# 07-FPGA.net
KiCad netlist of a schematic drawn in Altium Designer
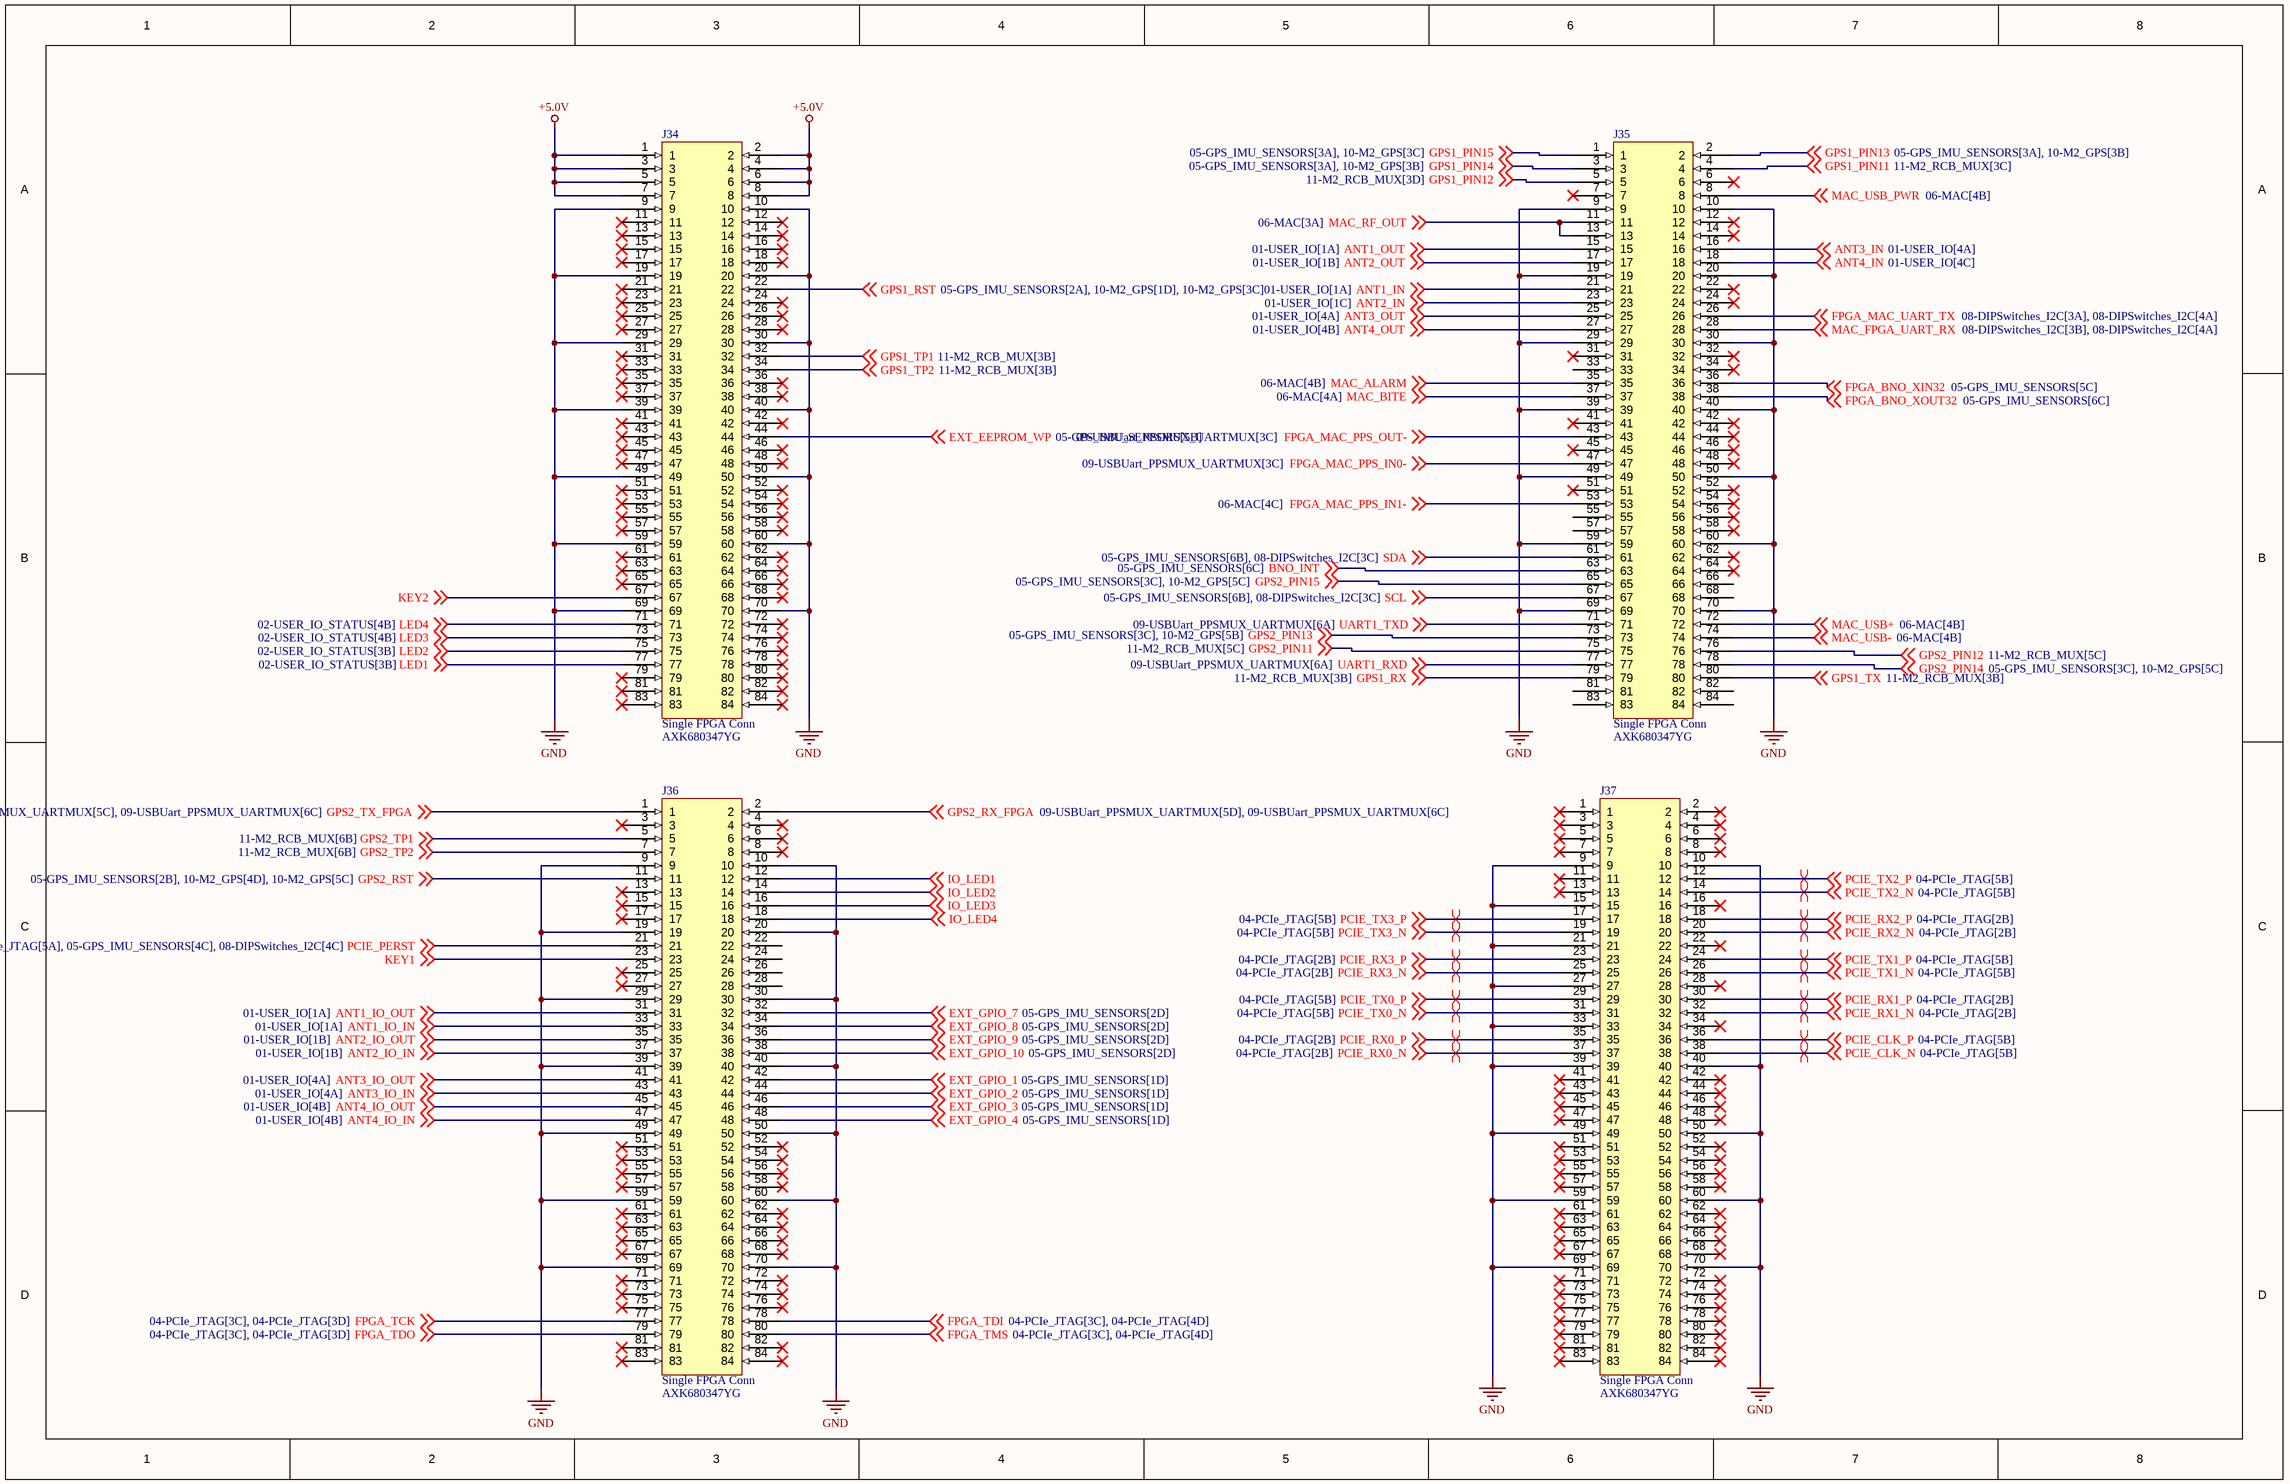
[diagram p0: 07-FPGA.SchDoc]

(export (version "E")
  (design (tool "Eeschema 10.0.6"))
  (components
    (comp (ref "J34")
      (value "Single FPGA Conn")
      (footprint "SingleFPGAConn")
      (fields (field (name "PART NUMBER") "AXK680347YG"))
      (libsource (lib "FPGA_CONN") (part "Single FPGA Conn"))
    )
    (comp (ref "J35")
      (value "Single FPGA Conn")
      (footprint "SingleFPGAConn")
      (fields (field (name "PART NUMBER") "AXK680347YG"))
      (libsource (lib "FPGA_CONN") (part "Single FPGA Conn"))
    )
    (comp (ref "J36")
      (value "Single FPGA Conn")
      (footprint "SingleFPGAConn")
      (fields (field (name "PART NUMBER") "AXK680347YG"))
      (libsource (lib "FPGA_CONN") (part "Single FPGA Conn"))
    )
    (comp (ref "J37")
      (value "Single FPGA Conn")
      (footprint "SingleFPGAConn")
      (fields (field (name "PART NUMBER") "AXK680347YG"))
      (libsource (lib "FPGA_CONN") (part "Single FPGA Conn"))
    )
  )
  (nets
    (net (code "1") (name "+5.0V") (class "Default")
      (node (ref "J34") (pin "1") (pinfunction "1_1") (pintype "input"))
      (node (ref "J34") (pin "2") (pinfunction "2_2") (pintype "input"))
      (node (ref "J34") (pin "3") (pinfunction "3_3") (pintype "input"))
      (node (ref "J34") (pin "4") (pinfunction "4_4") (pintype "input"))
      (node (ref "J34") (pin "5") (pinfunction "5_5") (pintype "input"))
      (node (ref "J34") (pin "6") (pinfunction "6_6") (pintype "input"))
      (node (ref "J34") (pin "7") (pinfunction "7_7") (pintype "input"))
      (node (ref "J34") (pin "8") (pinfunction "8_8") (pintype "input"))
    )
    (net (code "2") (name "ANT1_IN") (class "Default")
      (node (ref "J35") (pin "21") (pinfunction "21_21") (pintype "input"))
    )
    (net (code "3") (name "ANT1_IO_IN") (class "Default")
      (node (ref "J36") (pin "33") (pinfunction "33_33") (pintype "input"))
    )
    (net (code "4") (name "ANT1_IO_OUT") (class "Default")
      (node (ref "J36") (pin "31") (pinfunction "31_31") (pintype "input"))
    )
    (net (code "5") (name "ANT1_OUT") (class "Default")
      (node (ref "J35") (pin "15") (pinfunction "15_15") (pintype "input"))
    )
    (net (code "6") (name "ANT2_IN") (class "Default")
      (node (ref "J35") (pin "23") (pinfunction "23_23") (pintype "input"))
    )
    (net (code "7") (name "ANT2_IO_IN") (class "Default")
      (node (ref "J36") (pin "37") (pinfunction "37_37") (pintype "input"))
    )
    (net (code "8") (name "ANT2_IO_OUT") (class "Default")
      (node (ref "J36") (pin "35") (pinfunction "35_35") (pintype "input"))
    )
    (net (code "9") (name "ANT2_OUT") (class "Default")
      (node (ref "J35") (pin "17") (pinfunction "17_17") (pintype "input"))
    )
    (net (code "10") (name "ANT3_IN") (class "Default")
      (node (ref "J35") (pin "16") (pinfunction "16_16") (pintype "input"))
    )
    (net (code "11") (name "ANT3_IO_IN") (class "Default")
      (node (ref "J36") (pin "43") (pinfunction "43_43") (pintype "input"))
    )
    (net (code "12") (name "ANT3_IO_OUT") (class "Default")
      (node (ref "J36") (pin "41") (pinfunction "41_41") (pintype "input"))
    )
    (net (code "13") (name "ANT3_OUT") (class "Default")
      (node (ref "J35") (pin "25") (pinfunction "25_25") (pintype "input"))
    )
    (net (code "14") (name "ANT4_IN") (class "Default")
      (node (ref "J35") (pin "18") (pinfunction "18_18") (pintype "input"))
    )
    (net (code "15") (name "ANT4_IO_IN") (class "Default")
      (node (ref "J36") (pin "47") (pinfunction "47_47") (pintype "input"))
    )
    (net (code "16") (name "ANT4_IO_OUT") (class "Default")
      (node (ref "J36") (pin "45") (pinfunction "45_45") (pintype "input"))
    )
    (net (code "17") (name "ANT4_OUT") (class "Default")
      (node (ref "J35") (pin "27") (pinfunction "27_27") (pintype "input"))
    )
    (net (code "18") (name "BNO_INT") (class "Default")
      (node (ref "J35") (pin "63") (pinfunction "63_63") (pintype "input"))
    )
    (net (code "19") (name "EXT_EEPROM_WP") (class "Default")
      (node (ref "J34") (pin "44") (pinfunction "44_44") (pintype "input"))
    )
    (net (code "20") (name "EXT_GPIO_1") (class "Default")
      (node (ref "J36") (pin "42") (pinfunction "42_42") (pintype "input"))
    )
    (net (code "21") (name "EXT_GPIO_2") (class "Default")
      (node (ref "J36") (pin "44") (pinfunction "44_44") (pintype "input"))
    )
    (net (code "22") (name "EXT_GPIO_3") (class "Default")
      (node (ref "J36") (pin "46") (pinfunction "46_46") (pintype "input"))
    )
    (net (code "23") (name "EXT_GPIO_4") (class "Default")
      (node (ref "J36") (pin "48") (pinfunction "48_48") (pintype "input"))
    )
    (net (code "24") (name "EXT_GPIO_7") (class "Default")
      (node (ref "J36") (pin "32") (pinfunction "32_32") (pintype "input"))
    )
    (net (code "25") (name "EXT_GPIO_8") (class "Default")
      (node (ref "J36") (pin "34") (pinfunction "34_34") (pintype "input"))
    )
    (net (code "26") (name "EXT_GPIO_9") (class "Default")
      (node (ref "J36") (pin "36") (pinfunction "36_36") (pintype "input"))
    )
    (net (code "27") (name "EXT_GPIO_10") (class "Default")
      (node (ref "J36") (pin "38") (pinfunction "38_38") (pintype "input"))
    )
    (net (code "28") (name "FPGA_BNO_XIN32") (class "Default")
      (node (ref "J35") (pin "36") (pinfunction "36_36") (pintype "input"))
    )
    (net (code "29") (name "FPGA_BNO_XOUT32") (class "Default")
      (node (ref "J35") (pin "38") (pinfunction "38_38") (pintype "input"))
    )
    (net (code "30") (name "FPGA_MAC_PPS_IN0-") (class "Default")
      (node (ref "J35") (pin "47") (pinfunction "47_47") (pintype "input"))
    )
    (net (code "31") (name "FPGA_MAC_PPS_IN1-") (class "Default")
      (node (ref "J35") (pin "53") (pinfunction "53_53") (pintype "input"))
    )
    (net (code "32") (name "FPGA_MAC_PPS_OUT-") (class "Default")
      (node (ref "J35") (pin "43") (pinfunction "43_43") (pintype "input"))
    )
    (net (code "33") (name "FPGA_MAC_UART_TX") (class "Default")
      (node (ref "J35") (pin "26") (pinfunction "26_26") (pintype "input"))
    )
    (net (code "34") (name "FPGA_TCK") (class "Default")
      (node (ref "J36") (pin "77") (pinfunction "77_77") (pintype "input"))
    )
    (net (code "35") (name "FPGA_TDI") (class "Default")
      (node (ref "J36") (pin "78") (pinfunction "78_78") (pintype "input"))
    )
    (net (code "36") (name "FPGA_TDO") (class "Default")
      (node (ref "J36") (pin "79") (pinfunction "79_79") (pintype "input"))
    )
    (net (code "37") (name "FPGA_TMS") (class "Default")
      (node (ref "J36") (pin "80") (pinfunction "80_80") (pintype "input"))
    )
    (net (code "38") (name "GND") (class "Default")
      (node (ref "J34") (pin "10") (pinfunction "10_10") (pintype "input"))
      (node (ref "J34") (pin "19") (pinfunction "19_19") (pintype "input"))
      (node (ref "J34") (pin "20") (pinfunction "20_20") (pintype "input"))
      (node (ref "J34") (pin "29") (pinfunction "29_29") (pintype "input"))
      (node (ref "J34") (pin "30") (pinfunction "30_30") (pintype "input"))
      (node (ref "J34") (pin "39") (pinfunction "39_39") (pintype "input"))
      (node (ref "J34") (pin "40") (pinfunction "40_40") (pintype "input"))
      (node (ref "J34") (pin "49") (pinfunction "49_49") (pintype "input"))
      (node (ref "J34") (pin "50") (pinfunction "50_50") (pintype "input"))
      (node (ref "J34") (pin "59") (pinfunction "59_59") (pintype "input"))
      (node (ref "J34") (pin "60") (pinfunction "60_60") (pintype "input"))
      (node (ref "J34") (pin "69") (pinfunction "69_69") (pintype "input"))
      (node (ref "J34") (pin "70") (pinfunction "70_70") (pintype "input"))
      (node (ref "J34") (pin "9") (pinfunction "9_9") (pintype "input"))
      (node (ref "J35") (pin "10") (pinfunction "10_10") (pintype "input"))
      (node (ref "J35") (pin "19") (pinfunction "19_19") (pintype "input"))
      (node (ref "J35") (pin "20") (pinfunction "20_20") (pintype "input"))
      (node (ref "J35") (pin "29") (pinfunction "29_29") (pintype "input"))
      (node (ref "J35") (pin "30") (pinfunction "30_30") (pintype "input"))
      (node (ref "J35") (pin "39") (pinfunction "39_39") (pintype "input"))
      (node (ref "J35") (pin "40") (pinfunction "40_40") (pintype "input"))
      (node (ref "J35") (pin "49") (pinfunction "49_49") (pintype "input"))
      (node (ref "J35") (pin "50") (pinfunction "50_50") (pintype "input"))
      (node (ref "J35") (pin "59") (pinfunction "59_59") (pintype "input"))
      (node (ref "J35") (pin "60") (pinfunction "60_60") (pintype "input"))
      (node (ref "J35") (pin "69") (pinfunction "69_69") (pintype "input"))
      (node (ref "J35") (pin "70") (pinfunction "70_70") (pintype "input"))
      (node (ref "J35") (pin "9") (pinfunction "9_9") (pintype "input"))
      (node (ref "J36") (pin "10") (pinfunction "10_10") (pintype "input"))
      (node (ref "J36") (pin "19") (pinfunction "19_19") (pintype "input"))
      (node (ref "J36") (pin "20") (pinfunction "20_20") (pintype "input"))
      (node (ref "J36") (pin "29") (pinfunction "29_29") (pintype "input"))
      (node (ref "J36") (pin "30") (pinfunction "30_30") (pintype "input"))
      (node (ref "J36") (pin "39") (pinfunction "39_39") (pintype "input"))
      (node (ref "J36") (pin "40") (pinfunction "40_40") (pintype "input"))
      (node (ref "J36") (pin "49") (pinfunction "49_49") (pintype "input"))
      (node (ref "J36") (pin "50") (pinfunction "50_50") (pintype "input"))
      (node (ref "J36") (pin "59") (pinfunction "59_59") (pintype "input"))
      (node (ref "J36") (pin "60") (pinfunction "60_60") (pintype "input"))
      (node (ref "J36") (pin "69") (pinfunction "69_69") (pintype "input"))
      (node (ref "J36") (pin "70") (pinfunction "70_70") (pintype "input"))
      (node (ref "J36") (pin "9") (pinfunction "9_9") (pintype "input"))
      (node (ref "J37") (pin "10") (pinfunction "10_10") (pintype "input"))
      (node (ref "J37") (pin "15") (pinfunction "15_15") (pintype "input"))
      (node (ref "J37") (pin "21") (pinfunction "21_21") (pintype "input"))
      (node (ref "J37") (pin "27") (pinfunction "27_27") (pintype "input"))
      (node (ref "J37") (pin "33") (pinfunction "33_33") (pintype "input"))
      (node (ref "J37") (pin "39") (pinfunction "39_39") (pintype "input"))
      (node (ref "J37") (pin "40") (pinfunction "40_40") (pintype "input"))
      (node (ref "J37") (pin "49") (pinfunction "49_49") (pintype "input"))
      (node (ref "J37") (pin "50") (pinfunction "50_50") (pintype "input"))
      (node (ref "J37") (pin "59") (pinfunction "59_59") (pintype "input"))
      (node (ref "J37") (pin "60") (pinfunction "60_60") (pintype "input"))
      (node (ref "J37") (pin "69") (pinfunction "69_69") (pintype "input"))
      (node (ref "J37") (pin "70") (pinfunction "70_70") (pintype "input"))
      (node (ref "J37") (pin "9") (pinfunction "9_9") (pintype "input"))
    )
    (net (code "39") (name "GPS1_PIN11") (class "Default")
      (node (ref "J35") (pin "4") (pinfunction "4_4") (pintype "input"))
    )
    (net (code "40") (name "GPS1_PIN12") (class "Default")
      (node (ref "J35") (pin "5") (pinfunction "5_5") (pintype "input"))
    )
    (net (code "41") (name "GPS1_PIN13") (class "Default")
      (node (ref "J35") (pin "2") (pinfunction "2_2") (pintype "input"))
    )
    (net (code "42") (name "GPS1_PIN14") (class "Default")
      (node (ref "J35") (pin "3") (pinfunction "3_3") (pintype "input"))
    )
    (net (code "43") (name "GPS1_PIN15") (class "Default")
      (node (ref "J35") (pin "1") (pinfunction "1_1") (pintype "input"))
    )
    (net (code "44") (name "GPS1_RST") (class "Default")
      (node (ref "J34") (pin "22") (pinfunction "22_22") (pintype "input"))
    )
    (net (code "45") (name "GPS1_RX") (class "Default")
      (node (ref "J35") (pin "79") (pinfunction "79_79") (pintype "input"))
    )
    (net (code "46") (name "GPS1_TP1") (class "Default")
      (node (ref "J34") (pin "32") (pinfunction "32_32") (pintype "input"))
    )
    (net (code "47") (name "GPS1_TP2") (class "Default")
      (node (ref "J34") (pin "34") (pinfunction "34_34") (pintype "input"))
    )
    (net (code "48") (name "GPS1_TX") (class "Default")
      (node (ref "J35") (pin "80") (pinfunction "80_80") (pintype "input"))
    )
    (net (code "49") (name "GPS2_PIN11") (class "Default")
      (node (ref "J35") (pin "75") (pinfunction "75_75") (pintype "input"))
    )
    (net (code "50") (name "GPS2_PIN12") (class "Default")
      (node (ref "J35") (pin "76") (pinfunction "76_76") (pintype "input"))
    )
    (net (code "51") (name "GPS2_PIN13") (class "Default")
      (node (ref "J35") (pin "73") (pinfunction "73_73") (pintype "input"))
    )
    (net (code "52") (name "GPS2_PIN14") (class "Default")
      (node (ref "J35") (pin "78") (pinfunction "78_78") (pintype "input"))
    )
    (net (code "53") (name "GPS2_PIN15") (class "Default")
      (node (ref "J35") (pin "65") (pinfunction "65_65") (pintype "input"))
    )
    (net (code "54") (name "GPS2_RST") (class "Default")
      (node (ref "J36") (pin "11") (pinfunction "11_11") (pintype "input"))
    )
    (net (code "55") (name "GPS2_RX_FPGA") (class "Default")
      (node (ref "J36") (pin "2") (pinfunction "2_2") (pintype "input"))
    )
    (net (code "56") (name "GPS2_TP1") (class "Default")
      (node (ref "J36") (pin "5") (pinfunction "5_5") (pintype "input"))
    )
    (net (code "57") (name "GPS2_TP2") (class "Default")
      (node (ref "J36") (pin "7") (pinfunction "7_7") (pintype "input"))
    )
    (net (code "58") (name "GPS2_TX_FPGA") (class "Default")
      (node (ref "J36") (pin "1") (pinfunction "1_1") (pintype "input"))
    )
    (net (code "59") (name "IO_LED1") (class "Default")
      (node (ref "J36") (pin "12") (pinfunction "12_12") (pintype "input"))
    )
    (net (code "60") (name "IO_LED2") (class "Default")
      (node (ref "J36") (pin "14") (pinfunction "14_14") (pintype "input"))
    )
    (net (code "61") (name "IO_LED3") (class "Default")
      (node (ref "J36") (pin "16") (pinfunction "16_16") (pintype "input"))
    )
    (net (code "62") (name "IO_LED4") (class "Default")
      (node (ref "J36") (pin "18") (pinfunction "18_18") (pintype "input"))
    )
    (net (code "63") (name "KEY1") (class "Default")
      (node (ref "J36") (pin "23") (pinfunction "23_23") (pintype "input"))
    )
    (net (code "64") (name "KEY2") (class "Default")
      (node (ref "J34") (pin "67") (pinfunction "67_67") (pintype "input"))
    )
    (net (code "65") (name "LED1") (class "Default")
      (node (ref "J34") (pin "77") (pinfunction "77_77") (pintype "input"))
    )
    (net (code "66") (name "LED2") (class "Default")
      (node (ref "J34") (pin "75") (pinfunction "75_75") (pintype "input"))
    )
    (net (code "67") (name "LED3") (class "Default")
      (node (ref "J34") (pin "73") (pinfunction "73_73") (pintype "input"))
    )
    (net (code "68") (name "LED4") (class "Default")
      (node (ref "J34") (pin "71") (pinfunction "71_71") (pintype "input"))
    )
    (net (code "69") (name "MAC_ALARM") (class "Default")
      (node (ref "J35") (pin "35") (pinfunction "35_35") (pintype "input"))
    )
    (net (code "70") (name "MAC_BITE") (class "Default")
      (node (ref "J35") (pin "37") (pinfunction "37_37") (pintype "input"))
    )
    (net (code "71") (name "MAC_FPGA_UART_RX") (class "Default")
      (node (ref "J35") (pin "28") (pinfunction "28_28") (pintype "input"))
    )
    (net (code "72") (name "MAC_RF_OUT") (class "Default")
      (node (ref "J35") (pin "11") (pinfunction "11_11") (pintype "input"))
      (node (ref "J35") (pin "13") (pinfunction "13_13") (pintype "input"))
    )
    (net (code "73") (name "MAC_USB+") (class "Default")
      (node (ref "J35") (pin "72") (pinfunction "72_72") (pintype "input"))
    )
    (net (code "74") (name "MAC_USB-") (class "Default")
      (node (ref "J35") (pin "74") (pinfunction "74_74") (pintype "input"))
    )
    (net (code "75") (name "MAC_USB_PWR") (class "Default")
      (node (ref "J35") (pin "8") (pinfunction "8_8") (pintype "input"))
    )
    (net (code "76") (name "PCIE_CLK_N") (class "Default")
      (node (ref "J37") (pin "38") (pinfunction "38_38") (pintype "input"))
    )
    (net (code "77") (name "PCIE_CLK_P") (class "Default")
      (node (ref "J37") (pin "36") (pinfunction "36_36") (pintype "input"))
    )
    (net (code "78") (name "PCIE_PERST") (class "Default")
      (node (ref "J36") (pin "21") (pinfunction "21_21") (pintype "input"))
    )
    (net (code "79") (name "PCIE_RX0_N") (class "Default")
      (node (ref "J37") (pin "37") (pinfunction "37_37") (pintype "input"))
    )
    (net (code "80") (name "PCIE_RX0_P") (class "Default")
      (node (ref "J37") (pin "35") (pinfunction "35_35") (pintype "input"))
    )
    (net (code "81") (name "PCIE_RX1_N") (class "Default")
      (node (ref "J37") (pin "32") (pinfunction "32_32") (pintype "input"))
    )
    (net (code "82") (name "PCIE_RX1_P") (class "Default")
      (node (ref "J37") (pin "30") (pinfunction "30_30") (pintype "input"))
    )
    (net (code "83") (name "PCIE_RX2_N") (class "Default")
      (node (ref "J37") (pin "20") (pinfunction "20_20") (pintype "input"))
    )
    (net (code "84") (name "PCIE_RX2_P") (class "Default")
      (node (ref "J37") (pin "18") (pinfunction "18_18") (pintype "input"))
    )
    (net (code "85") (name "PCIE_RX3_N") (class "Default")
      (node (ref "J37") (pin "25") (pinfunction "25_25") (pintype "input"))
    )
    (net (code "86") (name "PCIE_RX3_P") (class "Default")
      (node (ref "J37") (pin "23") (pinfunction "23_23") (pintype "input"))
    )
    (net (code "87") (name "PCIE_TX0_N") (class "Default")
      (node (ref "J37") (pin "31") (pinfunction "31_31") (pintype "input"))
    )
    (net (code "88") (name "PCIE_TX0_P") (class "Default")
      (node (ref "J37") (pin "29") (pinfunction "29_29") (pintype "input"))
    )
    (net (code "89") (name "PCIE_TX1_N") (class "Default")
      (node (ref "J37") (pin "26") (pinfunction "26_26") (pintype "input"))
    )
    (net (code "90") (name "PCIE_TX1_P") (class "Default")
      (node (ref "J37") (pin "24") (pinfunction "24_24") (pintype "input"))
    )
    (net (code "91") (name "PCIE_TX2_N") (class "Default")
      (node (ref "J37") (pin "14") (pinfunction "14_14") (pintype "input"))
    )
    (net (code "92") (name "PCIE_TX2_P") (class "Default")
      (node (ref "J37") (pin "12") (pinfunction "12_12") (pintype "input"))
    )
    (net (code "93") (name "PCIE_TX3_N") (class "Default")
      (node (ref "J37") (pin "19") (pinfunction "19_19") (pintype "input"))
    )
    (net (code "94") (name "PCIE_TX3_P") (class "Default")
      (node (ref "J37") (pin "17") (pinfunction "17_17") (pintype "input"))
    )
    (net (code "95") (name "SCL") (class "Default")
      (node (ref "J35") (pin "67") (pinfunction "67_67") (pintype "input"))
    )
    (net (code "96") (name "SDA") (class "Default")
      (node (ref "J35") (pin "61") (pinfunction "61_61") (pintype "input"))
    )
    (net (code "97") (name "UART1_RXD") (class "Default")
      (node (ref "J35") (pin "77") (pinfunction "77_77") (pintype "input"))
    )
    (net (code "98") (name "UART1_TXD") (class "Default")
      (node (ref "J35") (pin "71") (pinfunction "71_71") (pintype "input"))
    )
    (net (code "99") (name "unconnected-(J34-Pad11)") (class "Default")
      (node (ref "J34") (pin "11") (pinfunction "11_11") (pintype "input+no_connect"))
    )
    (net (code "100") (name "unconnected-(J34-Pad12)") (class "Default")
      (node (ref "J34") (pin "12") (pinfunction "12_12") (pintype "input+no_connect"))
    )
    (net (code "101") (name "unconnected-(J34-Pad13)") (class "Default")
      (node (ref "J34") (pin "13") (pinfunction "13_13") (pintype "input+no_connect"))
    )
    (net (code "102") (name "unconnected-(J34-Pad14)") (class "Default")
      (node (ref "J34") (pin "14") (pinfunction "14_14") (pintype "input+no_connect"))
    )
    (net (code "103") (name "unconnected-(J34-Pad15)") (class "Default")
      (node (ref "J34") (pin "15") (pinfunction "15_15") (pintype "input+no_connect"))
    )
    (net (code "104") (name "unconnected-(J34-Pad16)") (class "Default")
      (node (ref "J34") (pin "16") (pinfunction "16_16") (pintype "input+no_connect"))
    )
    (net (code "105") (name "unconnected-(J34-Pad17)") (class "Default")
      (node (ref "J34") (pin "17") (pinfunction "17_17") (pintype "input+no_connect"))
    )
    (net (code "106") (name "unconnected-(J34-Pad18)") (class "Default")
      (node (ref "J34") (pin "18") (pinfunction "18_18") (pintype "input+no_connect"))
    )
    (net (code "107") (name "unconnected-(J34-Pad21)") (class "Default")
      (node (ref "J34") (pin "21") (pinfunction "21_21") (pintype "input+no_connect"))
    )
    (net (code "108") (name "unconnected-(J34-Pad23)") (class "Default")
      (node (ref "J34") (pin "23") (pinfunction "23_23") (pintype "input+no_connect"))
    )
    (net (code "109") (name "unconnected-(J34-Pad24)") (class "Default")
      (node (ref "J34") (pin "24") (pinfunction "24_24") (pintype "input+no_connect"))
    )
    (net (code "110") (name "unconnected-(J34-Pad25)") (class "Default")
      (node (ref "J34") (pin "25") (pinfunction "25_25") (pintype "input+no_connect"))
    )
    (net (code "111") (name "unconnected-(J34-Pad26)") (class "Default")
      (node (ref "J34") (pin "26") (pinfunction "26_26") (pintype "input+no_connect"))
    )
    (net (code "112") (name "unconnected-(J34-Pad27)") (class "Default")
      (node (ref "J34") (pin "27") (pinfunction "27_27") (pintype "input+no_connect"))
    )
    (net (code "113") (name "unconnected-(J34-Pad28)") (class "Default")
      (node (ref "J34") (pin "28") (pinfunction "28_28") (pintype "input+no_connect"))
    )
    (net (code "114") (name "unconnected-(J34-Pad31)") (class "Default")
      (node (ref "J34") (pin "31") (pinfunction "31_31") (pintype "input+no_connect"))
    )
    (net (code "115") (name "unconnected-(J34-Pad33)") (class "Default")
      (node (ref "J34") (pin "33") (pinfunction "33_33") (pintype "input+no_connect"))
    )
    (net (code "116") (name "unconnected-(J34-Pad35)") (class "Default")
      (node (ref "J34") (pin "35") (pinfunction "35_35") (pintype "input+no_connect"))
    )
    (net (code "117") (name "unconnected-(J34-Pad36)") (class "Default")
      (node (ref "J34") (pin "36") (pinfunction "36_36") (pintype "input+no_connect"))
    )
    (net (code "118") (name "unconnected-(J34-Pad37)") (class "Default")
      (node (ref "J34") (pin "37") (pinfunction "37_37") (pintype "input+no_connect"))
    )
    (net (code "119") (name "unconnected-(J34-Pad38)") (class "Default")
      (node (ref "J34") (pin "38") (pinfunction "38_38") (pintype "input+no_connect"))
    )
    (net (code "120") (name "unconnected-(J34-Pad41)") (class "Default")
      (node (ref "J34") (pin "41") (pinfunction "41_41") (pintype "input+no_connect"))
    )
    (net (code "121") (name "unconnected-(J34-Pad42)") (class "Default")
      (node (ref "J34") (pin "42") (pinfunction "42_42") (pintype "input+no_connect"))
    )
    (net (code "122") (name "unconnected-(J34-Pad43)") (class "Default")
      (node (ref "J34") (pin "43") (pinfunction "43_43") (pintype "input+no_connect"))
    )
    (net (code "123") (name "unconnected-(J34-Pad45)") (class "Default")
      (node (ref "J34") (pin "45") (pinfunction "45_45") (pintype "input+no_connect"))
    )
    (net (code "124") (name "unconnected-(J34-Pad46)") (class "Default")
      (node (ref "J34") (pin "46") (pinfunction "46_46") (pintype "input+no_connect"))
    )
    (net (code "125") (name "unconnected-(J34-Pad47)") (class "Default")
      (node (ref "J34") (pin "47") (pinfunction "47_47") (pintype "input+no_connect"))
    )
    (net (code "126") (name "unconnected-(J34-Pad48)") (class "Default")
      (node (ref "J34") (pin "48") (pinfunction "48_48") (pintype "input+no_connect"))
    )
    (net (code "127") (name "unconnected-(J34-Pad51)") (class "Default")
      (node (ref "J34") (pin "51") (pinfunction "51_51") (pintype "input+no_connect"))
    )
    (net (code "128") (name "unconnected-(J34-Pad52)") (class "Default")
      (node (ref "J34") (pin "52") (pinfunction "52_52") (pintype "input+no_connect"))
    )
    (net (code "129") (name "unconnected-(J34-Pad53)") (class "Default")
      (node (ref "J34") (pin "53") (pinfunction "53_53") (pintype "input+no_connect"))
    )
    (net (code "130") (name "unconnected-(J34-Pad54)") (class "Default")
      (node (ref "J34") (pin "54") (pinfunction "54_54") (pintype "input+no_connect"))
    )
    (net (code "131") (name "unconnected-(J34-Pad55)") (class "Default")
      (node (ref "J34") (pin "55") (pinfunction "55_55") (pintype "input+no_connect"))
    )
    (net (code "132") (name "unconnected-(J34-Pad56)") (class "Default")
      (node (ref "J34") (pin "56") (pinfunction "56_56") (pintype "input+no_connect"))
    )
    (net (code "133") (name "unconnected-(J34-Pad57)") (class "Default")
      (node (ref "J34") (pin "57") (pinfunction "57_57") (pintype "input+no_connect"))
    )
    (net (code "134") (name "unconnected-(J34-Pad58)") (class "Default")
      (node (ref "J34") (pin "58") (pinfunction "58_58") (pintype "input+no_connect"))
    )
    (net (code "135") (name "unconnected-(J34-Pad61)") (class "Default")
      (node (ref "J34") (pin "61") (pinfunction "61_61") (pintype "input+no_connect"))
    )
    (net (code "136") (name "unconnected-(J34-Pad62)") (class "Default")
      (node (ref "J34") (pin "62") (pinfunction "62_62") (pintype "input+no_connect"))
    )
    (net (code "137") (name "unconnected-(J34-Pad63)") (class "Default")
      (node (ref "J34") (pin "63") (pinfunction "63_63") (pintype "input+no_connect"))
    )
    (net (code "138") (name "unconnected-(J34-Pad64)") (class "Default")
      (node (ref "J34") (pin "64") (pinfunction "64_64") (pintype "input+no_connect"))
    )
    (net (code "139") (name "unconnected-(J34-Pad65)") (class "Default")
      (node (ref "J34") (pin "65") (pinfunction "65_65") (pintype "input+no_connect"))
    )
    (net (code "140") (name "unconnected-(J34-Pad66)") (class "Default")
      (node (ref "J34") (pin "66") (pinfunction "66_66") (pintype "input+no_connect"))
    )
    (net (code "141") (name "unconnected-(J34-Pad68)") (class "Default")
      (node (ref "J34") (pin "68") (pinfunction "68_68") (pintype "input+no_connect"))
    )
    (net (code "142") (name "unconnected-(J34-Pad72)") (class "Default")
      (node (ref "J34") (pin "72") (pinfunction "72_72") (pintype "input+no_connect"))
    )
    (net (code "143") (name "unconnected-(J34-Pad74)") (class "Default")
      (node (ref "J34") (pin "74") (pinfunction "74_74") (pintype "input+no_connect"))
    )
    (net (code "144") (name "unconnected-(J34-Pad76)") (class "Default")
      (node (ref "J34") (pin "76") (pinfunction "76_76") (pintype "input+no_connect"))
    )
    (net (code "145") (name "unconnected-(J34-Pad78)") (class "Default")
      (node (ref "J34") (pin "78") (pinfunction "78_78") (pintype "input+no_connect"))
    )
    (net (code "146") (name "unconnected-(J34-Pad79)") (class "Default")
      (node (ref "J34") (pin "79") (pinfunction "79_79") (pintype "input+no_connect"))
    )
    (net (code "147") (name "unconnected-(J34-Pad80)") (class "Default")
      (node (ref "J34") (pin "80") (pinfunction "80_80") (pintype "input+no_connect"))
    )
    (net (code "148") (name "unconnected-(J34-Pad81)") (class "Default")
      (node (ref "J34") (pin "81") (pinfunction "81_81") (pintype "input+no_connect"))
    )
    (net (code "149") (name "unconnected-(J34-Pad82)") (class "Default")
      (node (ref "J34") (pin "82") (pinfunction "82_82") (pintype "input+no_connect"))
    )
    (net (code "150") (name "unconnected-(J34-Pad83)") (class "Default")
      (node (ref "J34") (pin "83") (pinfunction "83_83") (pintype "input+no_connect"))
    )
    (net (code "151") (name "unconnected-(J34-Pad84)") (class "Default")
      (node (ref "J34") (pin "84") (pinfunction "84_84") (pintype "input+no_connect"))
    )
    (net (code "152") (name "unconnected-(J35-Pad6)") (class "Default")
      (node (ref "J35") (pin "6") (pinfunction "6_6") (pintype "input+no_connect"))
    )
    (net (code "153") (name "unconnected-(J35-Pad7)") (class "Default")
      (node (ref "J35") (pin "7") (pinfunction "7_7") (pintype "input+no_connect"))
    )
    (net (code "154") (name "unconnected-(J35-Pad12)") (class "Default")
      (node (ref "J35") (pin "12") (pinfunction "12_12") (pintype "input+no_connect"))
    )
    (net (code "155") (name "unconnected-(J35-Pad14)") (class "Default")
      (node (ref "J35") (pin "14") (pinfunction "14_14") (pintype "input+no_connect"))
    )
    (net (code "156") (name "unconnected-(J35-Pad22)") (class "Default")
      (node (ref "J35") (pin "22") (pinfunction "22_22") (pintype "input+no_connect"))
    )
    (net (code "157") (name "unconnected-(J35-Pad24)") (class "Default")
      (node (ref "J35") (pin "24") (pinfunction "24_24") (pintype "input+no_connect"))
    )
    (net (code "158") (name "unconnected-(J35-Pad31)") (class "Default")
      (node (ref "J35") (pin "31") (pinfunction "31_31") (pintype "input+no_connect"))
    )
    (net (code "159") (name "unconnected-(J35-Pad32)") (class "Default")
      (node (ref "J35") (pin "32") (pinfunction "32_32") (pintype "input+no_connect"))
    )
    (net (code "160") (name "unconnected-(J35-Pad33)") (class "Default")
      (node (ref "J35") (pin "33") (pinfunction "33_33") (pintype "input"))
    )
    (net (code "161") (name "unconnected-(J35-Pad34)") (class "Default")
      (node (ref "J35") (pin "34") (pinfunction "34_34") (pintype "input+no_connect"))
    )
    (net (code "162") (name "unconnected-(J35-Pad41)") (class "Default")
      (node (ref "J35") (pin "41") (pinfunction "41_41") (pintype "input+no_connect"))
    )
    (net (code "163") (name "unconnected-(J35-Pad42)") (class "Default")
      (node (ref "J35") (pin "42") (pinfunction "42_42") (pintype "input+no_connect"))
    )
    (net (code "164") (name "unconnected-(J35-Pad44)") (class "Default")
      (node (ref "J35") (pin "44") (pinfunction "44_44") (pintype "input+no_connect"))
    )
    (net (code "165") (name "unconnected-(J35-Pad45)") (class "Default")
      (node (ref "J35") (pin "45") (pinfunction "45_45") (pintype "input+no_connect"))
    )
    (net (code "166") (name "unconnected-(J35-Pad46)") (class "Default")
      (node (ref "J35") (pin "46") (pinfunction "46_46") (pintype "input+no_connect"))
    )
    (net (code "167") (name "unconnected-(J35-Pad48)") (class "Default")
      (node (ref "J35") (pin "48") (pinfunction "48_48") (pintype "input+no_connect"))
    )
    (net (code "168") (name "unconnected-(J35-Pad51)") (class "Default")
      (node (ref "J35") (pin "51") (pinfunction "51_51") (pintype "input+no_connect"))
    )
    (net (code "169") (name "unconnected-(J35-Pad52)") (class "Default")
      (node (ref "J35") (pin "52") (pinfunction "52_52") (pintype "input+no_connect"))
    )
    (net (code "170") (name "unconnected-(J35-Pad54)") (class "Default")
      (node (ref "J35") (pin "54") (pinfunction "54_54") (pintype "input+no_connect"))
    )
    (net (code "171") (name "unconnected-(J35-Pad55)") (class "Default")
      (node (ref "J35") (pin "55") (pinfunction "55_55") (pintype "input"))
    )
    (net (code "172") (name "unconnected-(J35-Pad56)") (class "Default")
      (node (ref "J35") (pin "56") (pinfunction "56_56") (pintype "input+no_connect"))
    )
    (net (code "173") (name "unconnected-(J35-Pad57)") (class "Default")
      (node (ref "J35") (pin "57") (pinfunction "57_57") (pintype "input"))
    )
    (net (code "174") (name "unconnected-(J35-Pad58)") (class "Default")
      (node (ref "J35") (pin "58") (pinfunction "58_58") (pintype "input+no_connect"))
    )
    (net (code "175") (name "unconnected-(J35-Pad62)") (class "Default")
      (node (ref "J35") (pin "62") (pinfunction "62_62") (pintype "input+no_connect"))
    )
    (net (code "176") (name "unconnected-(J35-Pad64)") (class "Default")
      (node (ref "J35") (pin "64") (pinfunction "64_64") (pintype "input+no_connect"))
    )
    (net (code "177") (name "unconnected-(J35-Pad66)") (class "Default")
      (node (ref "J35") (pin "66") (pinfunction "66_66") (pintype "input"))
    )
    (net (code "178") (name "unconnected-(J35-Pad68)") (class "Default")
      (node (ref "J35") (pin "68") (pinfunction "68_68") (pintype "input"))
    )
    (net (code "179") (name "unconnected-(J35-Pad81)") (class "Default")
      (node (ref "J35") (pin "81") (pinfunction "81_81") (pintype "input"))
    )
    (net (code "180") (name "unconnected-(J35-Pad82)") (class "Default")
      (node (ref "J35") (pin "82") (pinfunction "82_82") (pintype "input"))
    )
    (net (code "181") (name "unconnected-(J35-Pad83)") (class "Default")
      (node (ref "J35") (pin "83") (pinfunction "83_83") (pintype "input"))
    )
    (net (code "182") (name "unconnected-(J35-Pad84)") (class "Default")
      (node (ref "J35") (pin "84") (pinfunction "84_84") (pintype "input"))
    )
    (net (code "183") (name "unconnected-(J36-Pad3)") (class "Default")
      (node (ref "J36") (pin "3") (pinfunction "3_3") (pintype "input+no_connect"))
    )
    (net (code "184") (name "unconnected-(J36-Pad4)") (class "Default")
      (node (ref "J36") (pin "4") (pinfunction "4_4") (pintype "input+no_connect"))
    )
    (net (code "185") (name "unconnected-(J36-Pad6)") (class "Default")
      (node (ref "J36") (pin "6") (pinfunction "6_6") (pintype "input+no_connect"))
    )
    (net (code "186") (name "unconnected-(J36-Pad8)") (class "Default")
      (node (ref "J36") (pin "8") (pinfunction "8_8") (pintype "input+no_connect"))
    )
    (net (code "187") (name "unconnected-(J36-Pad13)") (class "Default")
      (node (ref "J36") (pin "13") (pinfunction "13_13") (pintype "input+no_connect"))
    )
    (net (code "188") (name "unconnected-(J36-Pad15)") (class "Default")
      (node (ref "J36") (pin "15") (pinfunction "15_15") (pintype "input+no_connect"))
    )
    (net (code "189") (name "unconnected-(J36-Pad17)") (class "Default")
      (node (ref "J36") (pin "17") (pinfunction "17_17") (pintype "input+no_connect"))
    )
    (net (code "190") (name "unconnected-(J36-Pad22)") (class "Default")
      (node (ref "J36") (pin "22") (pinfunction "22_22") (pintype "input"))
    )
    (net (code "191") (name "unconnected-(J36-Pad24)") (class "Default")
      (node (ref "J36") (pin "24") (pinfunction "24_24") (pintype "input"))
    )
    (net (code "192") (name "unconnected-(J36-Pad25)") (class "Default")
      (node (ref "J36") (pin "25") (pinfunction "25_25") (pintype "input+no_connect"))
    )
    (net (code "193") (name "unconnected-(J36-Pad26)") (class "Default")
      (node (ref "J36") (pin "26") (pinfunction "26_26") (pintype "input"))
    )
    (net (code "194") (name "unconnected-(J36-Pad27)") (class "Default")
      (node (ref "J36") (pin "27") (pinfunction "27_27") (pintype "input+no_connect"))
    )
    (net (code "195") (name "unconnected-(J36-Pad28)") (class "Default")
      (node (ref "J36") (pin "28") (pinfunction "28_28") (pintype "input"))
    )
    (net (code "196") (name "unconnected-(J36-Pad51)") (class "Default")
      (node (ref "J36") (pin "51") (pinfunction "51_51") (pintype "input+no_connect"))
    )
    (net (code "197") (name "unconnected-(J36-Pad52)") (class "Default")
      (node (ref "J36") (pin "52") (pinfunction "52_52") (pintype "input+no_connect"))
    )
    (net (code "198") (name "unconnected-(J36-Pad53)") (class "Default")
      (node (ref "J36") (pin "53") (pinfunction "53_53") (pintype "input+no_connect"))
    )
    (net (code "199") (name "unconnected-(J36-Pad54)") (class "Default")
      (node (ref "J36") (pin "54") (pinfunction "54_54") (pintype "input+no_connect"))
    )
    (net (code "200") (name "unconnected-(J36-Pad55)") (class "Default")
      (node (ref "J36") (pin "55") (pinfunction "55_55") (pintype "input+no_connect"))
    )
    (net (code "201") (name "unconnected-(J36-Pad56)") (class "Default")
      (node (ref "J36") (pin "56") (pinfunction "56_56") (pintype "input+no_connect"))
    )
    (net (code "202") (name "unconnected-(J36-Pad57)") (class "Default")
      (node (ref "J36") (pin "57") (pinfunction "57_57") (pintype "input+no_connect"))
    )
    (net (code "203") (name "unconnected-(J36-Pad58)") (class "Default")
      (node (ref "J36") (pin "58") (pinfunction "58_58") (pintype "input+no_connect"))
    )
    (net (code "204") (name "unconnected-(J36-Pad61)") (class "Default")
      (node (ref "J36") (pin "61") (pinfunction "61_61") (pintype "input+no_connect"))
    )
    (net (code "205") (name "unconnected-(J36-Pad62)") (class "Default")
      (node (ref "J36") (pin "62") (pinfunction "62_62") (pintype "input+no_connect"))
    )
    (net (code "206") (name "unconnected-(J36-Pad63)") (class "Default")
      (node (ref "J36") (pin "63") (pinfunction "63_63") (pintype "input+no_connect"))
    )
    (net (code "207") (name "unconnected-(J36-Pad64)") (class "Default")
      (node (ref "J36") (pin "64") (pinfunction "64_64") (pintype "input+no_connect"))
    )
    (net (code "208") (name "unconnected-(J36-Pad65)") (class "Default")
      (node (ref "J36") (pin "65") (pinfunction "65_65") (pintype "input+no_connect"))
    )
    (net (code "209") (name "unconnected-(J36-Pad66)") (class "Default")
      (node (ref "J36") (pin "66") (pinfunction "66_66") (pintype "input+no_connect"))
    )
    (net (code "210") (name "unconnected-(J36-Pad67)") (class "Default")
      (node (ref "J36") (pin "67") (pinfunction "67_67") (pintype "input+no_connect"))
    )
    (net (code "211") (name "unconnected-(J36-Pad68)") (class "Default")
      (node (ref "J36") (pin "68") (pinfunction "68_68") (pintype "input+no_connect"))
    )
    (net (code "212") (name "unconnected-(J36-Pad71)") (class "Default")
      (node (ref "J36") (pin "71") (pinfunction "71_71") (pintype "input+no_connect"))
    )
    (net (code "213") (name "unconnected-(J36-Pad72)") (class "Default")
      (node (ref "J36") (pin "72") (pinfunction "72_72") (pintype "input+no_connect"))
    )
    (net (code "214") (name "unconnected-(J36-Pad73)") (class "Default")
      (node (ref "J36") (pin "73") (pinfunction "73_73") (pintype "input+no_connect"))
    )
    (net (code "215") (name "unconnected-(J36-Pad74)") (class "Default")
      (node (ref "J36") (pin "74") (pinfunction "74_74") (pintype "input+no_connect"))
    )
    (net (code "216") (name "unconnected-(J36-Pad75)") (class "Default")
      (node (ref "J36") (pin "75") (pinfunction "75_75") (pintype "input+no_connect"))
    )
    (net (code "217") (name "unconnected-(J36-Pad76)") (class "Default")
      (node (ref "J36") (pin "76") (pinfunction "76_76") (pintype "input+no_connect"))
    )
    (net (code "218") (name "unconnected-(J36-Pad81)") (class "Default")
      (node (ref "J36") (pin "81") (pinfunction "81_81") (pintype "input+no_connect"))
    )
    (net (code "219") (name "unconnected-(J36-Pad82)") (class "Default")
      (node (ref "J36") (pin "82") (pinfunction "82_82") (pintype "input+no_connect"))
    )
    (net (code "220") (name "unconnected-(J36-Pad83)") (class "Default")
      (node (ref "J36") (pin "83") (pinfunction "83_83") (pintype "input+no_connect"))
    )
    (net (code "221") (name "unconnected-(J36-Pad84)") (class "Default")
      (node (ref "J36") (pin "84") (pinfunction "84_84") (pintype "input+no_connect"))
    )
    (net (code "222") (name "unconnected-(J37-Pad1)") (class "Default")
      (node (ref "J37") (pin "1") (pinfunction "1_1") (pintype "input+no_connect"))
    )
    (net (code "223") (name "unconnected-(J37-Pad2)") (class "Default")
      (node (ref "J37") (pin "2") (pinfunction "2_2") (pintype "input+no_connect"))
    )
    (net (code "224") (name "unconnected-(J37-Pad3)") (class "Default")
      (node (ref "J37") (pin "3") (pinfunction "3_3") (pintype "input+no_connect"))
    )
    (net (code "225") (name "unconnected-(J37-Pad4)") (class "Default")
      (node (ref "J37") (pin "4") (pinfunction "4_4") (pintype "input+no_connect"))
    )
    (net (code "226") (name "unconnected-(J37-Pad5)") (class "Default")
      (node (ref "J37") (pin "5") (pinfunction "5_5") (pintype "input+no_connect"))
    )
    (net (code "227") (name "unconnected-(J37-Pad6)") (class "Default")
      (node (ref "J37") (pin "6") (pinfunction "6_6") (pintype "input+no_connect"))
    )
    (net (code "228") (name "unconnected-(J37-Pad7)") (class "Default")
      (node (ref "J37") (pin "7") (pinfunction "7_7") (pintype "input+no_connect"))
    )
    (net (code "229") (name "unconnected-(J37-Pad8)") (class "Default")
      (node (ref "J37") (pin "8") (pinfunction "8_8") (pintype "input+no_connect"))
    )
    (net (code "230") (name "unconnected-(J37-Pad11)") (class "Default")
      (node (ref "J37") (pin "11") (pinfunction "11_11") (pintype "input+no_connect"))
    )
    (net (code "231") (name "unconnected-(J37-Pad13)") (class "Default")
      (node (ref "J37") (pin "13") (pinfunction "13_13") (pintype "input+no_connect"))
    )
    (net (code "232") (name "unconnected-(J37-Pad16)") (class "Default")
      (node (ref "J37") (pin "16") (pinfunction "16_16") (pintype "input+no_connect"))
    )
    (net (code "233") (name "unconnected-(J37-Pad22)") (class "Default")
      (node (ref "J37") (pin "22") (pinfunction "22_22") (pintype "input+no_connect"))
    )
    (net (code "234") (name "unconnected-(J37-Pad28)") (class "Default")
      (node (ref "J37") (pin "28") (pinfunction "28_28") (pintype "input+no_connect"))
    )
    (net (code "235") (name "unconnected-(J37-Pad34)") (class "Default")
      (node (ref "J37") (pin "34") (pinfunction "34_34") (pintype "input+no_connect"))
    )
    (net (code "236") (name "unconnected-(J37-Pad41)") (class "Default")
      (node (ref "J37") (pin "41") (pinfunction "41_41") (pintype "input+no_connect"))
    )
    (net (code "237") (name "unconnected-(J37-Pad42)") (class "Default")
      (node (ref "J37") (pin "42") (pinfunction "42_42") (pintype "input+no_connect"))
    )
    (net (code "238") (name "unconnected-(J37-Pad43)") (class "Default")
      (node (ref "J37") (pin "43") (pinfunction "43_43") (pintype "input+no_connect"))
    )
    (net (code "239") (name "unconnected-(J37-Pad44)") (class "Default")
      (node (ref "J37") (pin "44") (pinfunction "44_44") (pintype "input+no_connect"))
    )
    (net (code "240") (name "unconnected-(J37-Pad45)") (class "Default")
      (node (ref "J37") (pin "45") (pinfunction "45_45") (pintype "input+no_connect"))
    )
    (net (code "241") (name "unconnected-(J37-Pad46)") (class "Default")
      (node (ref "J37") (pin "46") (pinfunction "46_46") (pintype "input+no_connect"))
    )
    (net (code "242") (name "unconnected-(J37-Pad47)") (class "Default")
      (node (ref "J37") (pin "47") (pinfunction "47_47") (pintype "input+no_connect"))
    )
    (net (code "243") (name "unconnected-(J37-Pad48)") (class "Default")
      (node (ref "J37") (pin "48") (pinfunction "48_48") (pintype "input+no_connect"))
    )
    (net (code "244") (name "unconnected-(J37-Pad51)") (class "Default")
      (node (ref "J37") (pin "51") (pinfunction "51_51") (pintype "input+no_connect"))
    )
    (net (code "245") (name "unconnected-(J37-Pad52)") (class "Default")
      (node (ref "J37") (pin "52") (pinfunction "52_52") (pintype "input+no_connect"))
    )
    (net (code "246") (name "unconnected-(J37-Pad53)") (class "Default")
      (node (ref "J37") (pin "53") (pinfunction "53_53") (pintype "input+no_connect"))
    )
    (net (code "247") (name "unconnected-(J37-Pad54)") (class "Default")
      (node (ref "J37") (pin "54") (pinfunction "54_54") (pintype "input+no_connect"))
    )
    (net (code "248") (name "unconnected-(J37-Pad55)") (class "Default")
      (node (ref "J37") (pin "55") (pinfunction "55_55") (pintype "input+no_connect"))
    )
    (net (code "249") (name "unconnected-(J37-Pad56)") (class "Default")
      (node (ref "J37") (pin "56") (pinfunction "56_56") (pintype "input+no_connect"))
    )
    (net (code "250") (name "unconnected-(J37-Pad57)") (class "Default")
      (node (ref "J37") (pin "57") (pinfunction "57_57") (pintype "input+no_connect"))
    )
    (net (code "251") (name "unconnected-(J37-Pad58)") (class "Default")
      (node (ref "J37") (pin "58") (pinfunction "58_58") (pintype "input+no_connect"))
    )
    (net (code "252") (name "unconnected-(J37-Pad61)") (class "Default")
      (node (ref "J37") (pin "61") (pinfunction "61_61") (pintype "input+no_connect"))
    )
    (net (code "253") (name "unconnected-(J37-Pad62)") (class "Default")
      (node (ref "J37") (pin "62") (pinfunction "62_62") (pintype "input+no_connect"))
    )
    (net (code "254") (name "unconnected-(J37-Pad63)") (class "Default")
      (node (ref "J37") (pin "63") (pinfunction "63_63") (pintype "input+no_connect"))
    )
    (net (code "255") (name "unconnected-(J37-Pad64)") (class "Default")
      (node (ref "J37") (pin "64") (pinfunction "64_64") (pintype "input+no_connect"))
    )
    (net (code "256") (name "unconnected-(J37-Pad65)") (class "Default")
      (node (ref "J37") (pin "65") (pinfunction "65_65") (pintype "input+no_connect"))
    )
    (net (code "257") (name "unconnected-(J37-Pad66)") (class "Default")
      (node (ref "J37") (pin "66") (pinfunction "66_66") (pintype "input+no_connect"))
    )
    (net (code "258") (name "unconnected-(J37-Pad67)") (class "Default")
      (node (ref "J37") (pin "67") (pinfunction "67_67") (pintype "input+no_connect"))
    )
    (net (code "259") (name "unconnected-(J37-Pad68)") (class "Default")
      (node (ref "J37") (pin "68") (pinfunction "68_68") (pintype "input+no_connect"))
    )
    (net (code "260") (name "unconnected-(J37-Pad71)") (class "Default")
      (node (ref "J37") (pin "71") (pinfunction "71_71") (pintype "input+no_connect"))
    )
    (net (code "261") (name "unconnected-(J37-Pad72)") (class "Default")
      (node (ref "J37") (pin "72") (pinfunction "72_72") (pintype "input+no_connect"))
    )
    (net (code "262") (name "unconnected-(J37-Pad73)") (class "Default")
      (node (ref "J37") (pin "73") (pinfunction "73_73") (pintype "input+no_connect"))
    )
    (net (code "263") (name "unconnected-(J37-Pad74)") (class "Default")
      (node (ref "J37") (pin "74") (pinfunction "74_74") (pintype "input+no_connect"))
    )
    (net (code "264") (name "unconnected-(J37-Pad75)") (class "Default")
      (node (ref "J37") (pin "75") (pinfunction "75_75") (pintype "input+no_connect"))
    )
    (net (code "265") (name "unconnected-(J37-Pad76)") (class "Default")
      (node (ref "J37") (pin "76") (pinfunction "76_76") (pintype "input+no_connect"))
    )
    (net (code "266") (name "unconnected-(J37-Pad77)") (class "Default")
      (node (ref "J37") (pin "77") (pinfunction "77_77") (pintype "input+no_connect"))
    )
    (net (code "267") (name "unconnected-(J37-Pad78)") (class "Default")
      (node (ref "J37") (pin "78") (pinfunction "78_78") (pintype "input+no_connect"))
    )
    (net (code "268") (name "unconnected-(J37-Pad79)") (class "Default")
      (node (ref "J37") (pin "79") (pinfunction "79_79") (pintype "input+no_connect"))
    )
    (net (code "269") (name "unconnected-(J37-Pad80)") (class "Default")
      (node (ref "J37") (pin "80") (pinfunction "80_80") (pintype "input+no_connect"))
    )
    (net (code "270") (name "unconnected-(J37-Pad81)") (class "Default")
      (node (ref "J37") (pin "81") (pinfunction "81_81") (pintype "input+no_connect"))
    )
    (net (code "271") (name "unconnected-(J37-Pad82)") (class "Default")
      (node (ref "J37") (pin "82") (pinfunction "82_82") (pintype "input+no_connect"))
    )
    (net (code "272") (name "unconnected-(J37-Pad83)") (class "Default")
      (node (ref "J37") (pin "83") (pinfunction "83_83") (pintype "input+no_connect"))
    )
    (net (code "273") (name "unconnected-(J37-Pad84)") (class "Default")
      (node (ref "J37") (pin "84") (pinfunction "84_84") (pintype "input+no_connect"))
    )
  )
)
